# 7_VGA.net
KiCad netlist of a schematic drawn in Altium Designer
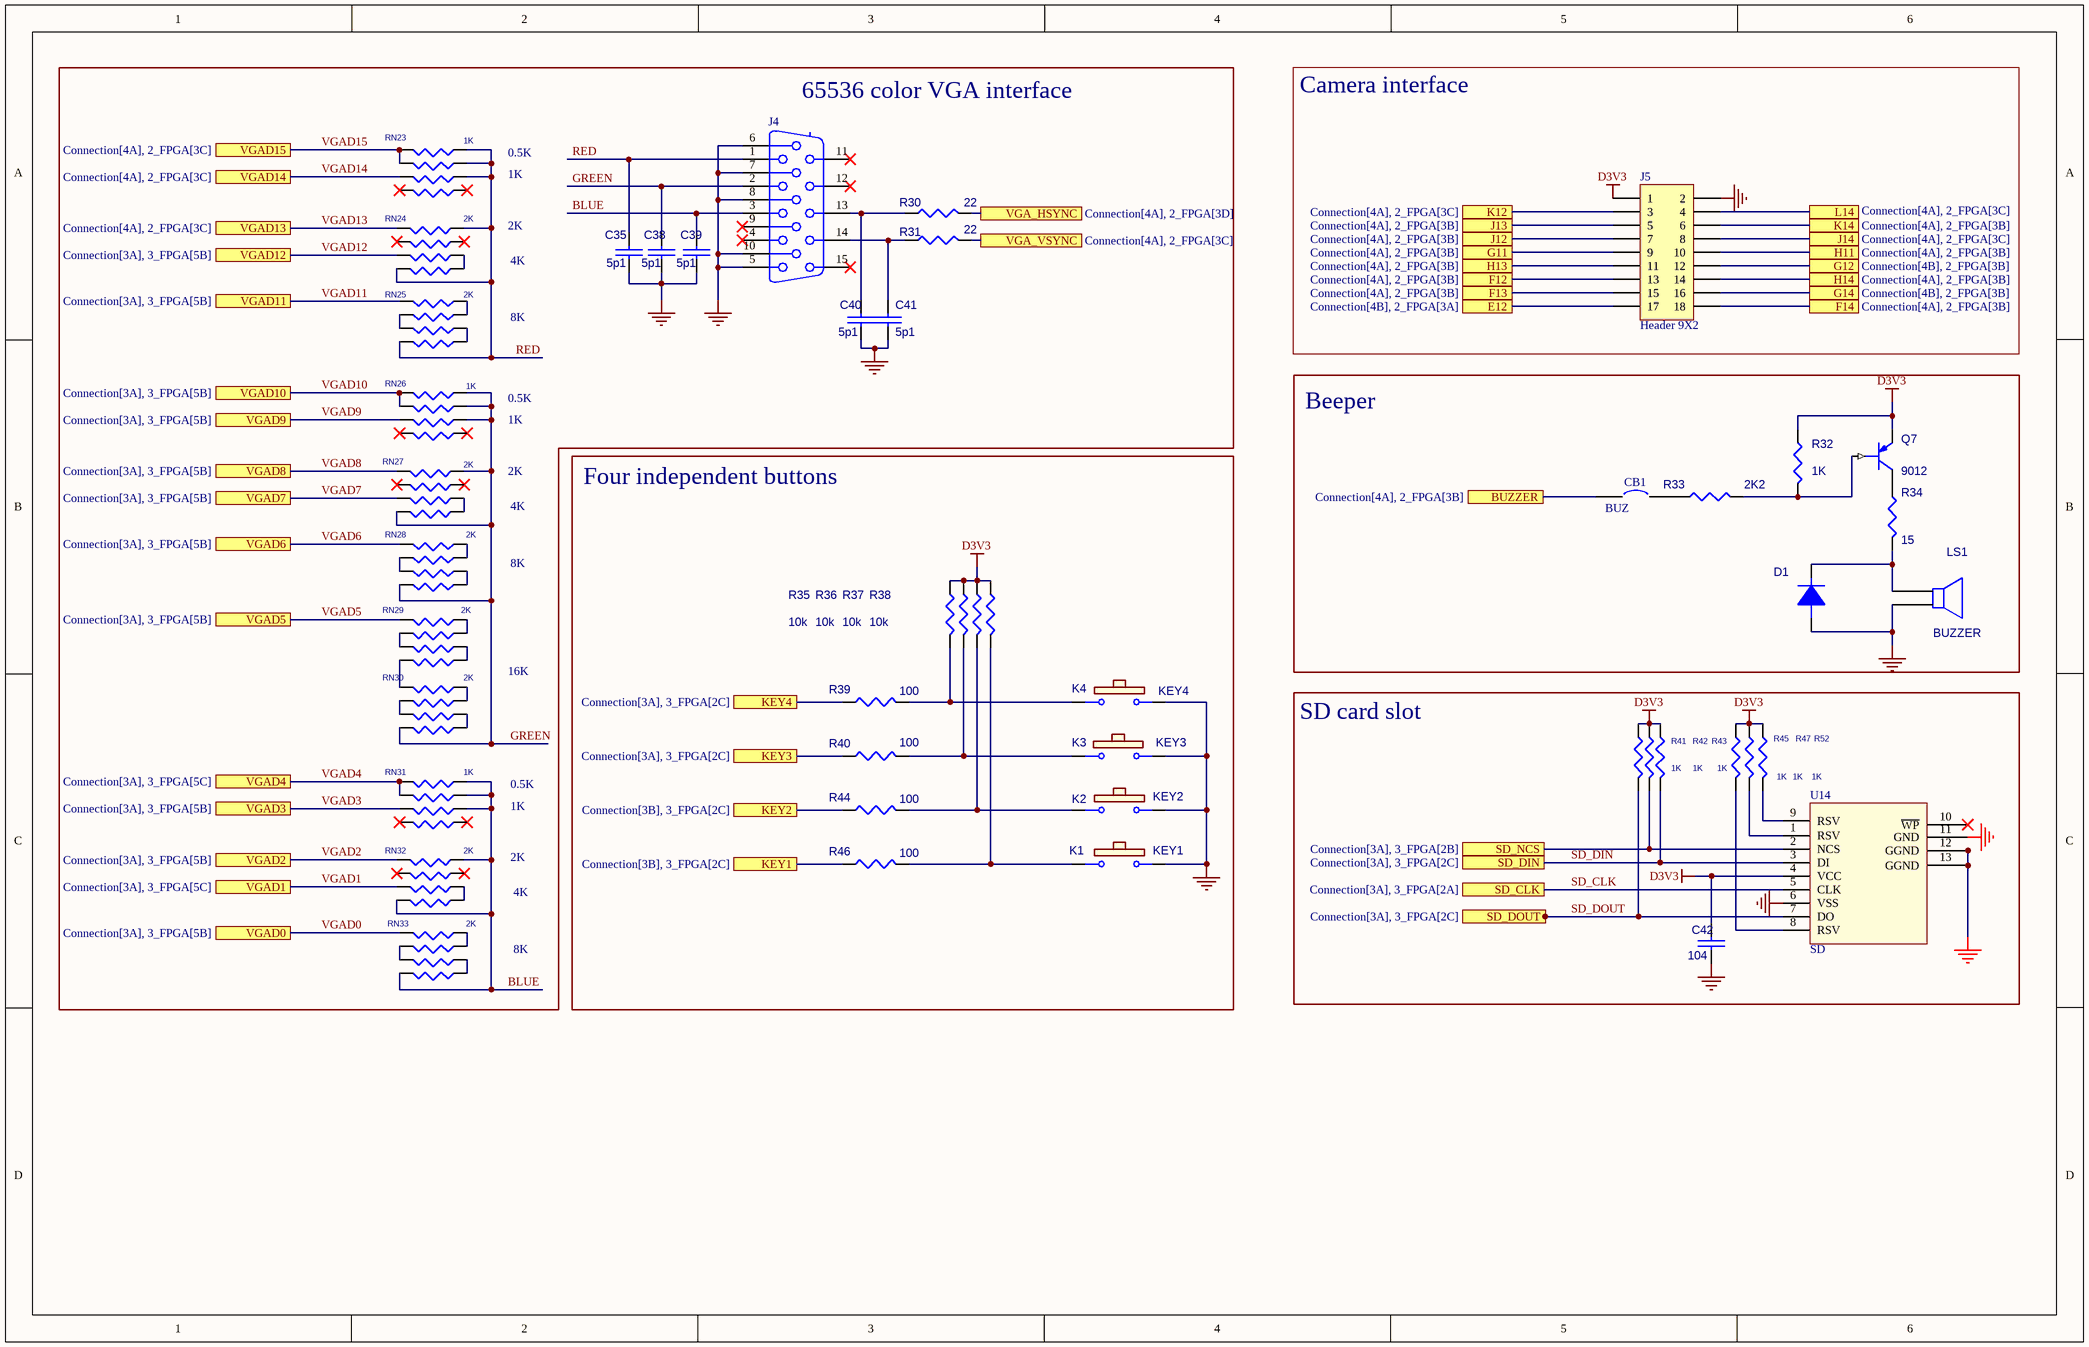
[diagram p0: 7_VGA.SchDoc]

(export (version "E")
  (design (tool "Eeschema 10.0.6"))
  (components
    (comp (ref "C35") (value "5p1") (footprint "0603 Cap") (libsource (lib "SPARTAN6") (part "C_Dup4")))
    (comp (ref "C38") (value "5p1") (footprint "0603 Cap") (libsource (lib "SPARTAN6") (part "C_Dup4")))
    (comp (ref "C39") (value "5p1") (footprint "0603 Cap") (libsource (lib "SPARTAN6") (part "C_Dup4")))
    (comp (ref "C40") (value "5p1") (footprint "0603 Cap") (libsource (lib "SPARTAN6") (part "C_Dup4")))
    (comp (ref "C41") (value "5p1") (footprint "0603 Cap") (libsource (lib "SPARTAN6") (part "C_Dup4")))
    (comp (ref "C42") (value "104") (footprint "0402 Cap") (libsource (lib "SPARTAN6") (part "C_Dup3")))
    (comp (ref "CB1")
      (value "BUZ")
      (footprint "SIP2")
      (description "Circuit Breaker")
      (fields (field (name "PUBLISHER") "Altium Limited"))
      (libsource (lib "Miscellaneous Devices") (part "Circuit Breaker"))
    )
    (comp (ref "D1") (value "~") (footprint "1206") (libsource (lib "Xilinx Spartan-6") (part "4148")))
    (comp (ref "J4")
      (value "~")
      (footprint "VGA")
      (description "Receptacle Assembly, 15-Pin, Sim Line Connector")
      (fields (field (name "PUBLISHER") "Altium Limited"))
      (libsource (lib "Xilinx Spartan-6") (part "Connector 15"))
    )
    (comp (ref "J5")
      (value "Header 9X2")
      (footprint "HDR2X9")
      (description "Header, 9-Pin, Dual row")
      (fields (field (name "PUBLISHER") "Altium Limited"))
      (libsource (lib "Miscellaneous Connectors") (part "Header 9X2"))
    )
    (comp (ref "K1") (value "KEY1") (footprint "KEY735SO") (libsource (lib "*") (part "KEYB")))
    (comp (ref "K2") (value "KEY2") (footprint "KEY735SO") (libsource (lib "*") (part "KEYB")))
    (comp (ref "K3") (value "KEY3") (footprint "KEY735SO") (libsource (lib "") (part "KEYB_1")))
    (comp (ref "K4") (value "KEY4") (footprint "KEY735SO") (libsource (lib "*") (part "KEYB")))
    (comp (ref "LS1") (value "BUZZER") (libsource (lib "*") (part "SPEAKER")))
    (comp (ref "Q7") (value "9012") (footprint "SOT23") (libsource (lib "*") (part "PNP")))
    (comp (ref "R30") (value "22") (footprint "0603") (libsource (lib "*") (part "R")))
    (comp (ref "R31") (value "22") (footprint "0603") (libsource (lib "*") (part "R")))
    (comp (ref "R32") (value "1K") (footprint "0603") (libsource (lib "*") (part "R_Dup3")))
    (comp (ref "R33") (value "2K2") (footprint "0603") (libsource (lib "*") (part "R_Dup3")))
    (comp (ref "R34") (value "15") (footprint "0603") (libsource (lib "*") (part "R_Dup3")))
    (comp (ref "R35") (value "10k") (footprint "0603") (libsource (lib "*") (part "R_Dup2")))
    (comp (ref "R36") (value "10k") (footprint "0603") (libsource (lib "*") (part "R_Dup2")))
    (comp (ref "R37") (value "10k") (footprint "0603") (libsource (lib "*") (part "R_Dup2")))
    (comp (ref "R38") (value "10k") (footprint "0603") (libsource (lib "*") (part "R_Dup2")))
    (comp (ref "R39") (value "100") (footprint "0603") (libsource (lib "*") (part "R_Dup2")))
    (comp (ref "R40") (value "100") (footprint "0603") (libsource (lib "*") (part "R_Dup2")))
    (comp (ref "R41") (value "1K") (footprint "0603") (libsource (lib "*") (part "R")))
    (comp (ref "R42") (value "1K") (footprint "0603") (libsource (lib "*") (part "R")))
    (comp (ref "R43") (value "1K") (footprint "0603") (libsource (lib "*") (part "R")))
    (comp (ref "R44") (value "100") (footprint "0603") (libsource (lib "*") (part "R_Dup2")))
    (comp (ref "R45") (value "1K") (footprint "0603") (libsource (lib "*") (part "R")))
    (comp (ref "R46") (value "100") (footprint "0603") (libsource (lib "*") (part "R_Dup2")))
    (comp (ref "R47") (value "1K") (footprint "0603") (libsource (lib "*") (part "R")))
    (comp (ref "R52") (value "1K") (footprint "0603") (libsource (lib "*") (part "R")))
    (comp (ref "RN23") (value "1K") (footprint "RN-8P") (libsource (lib "*") (part "RN_Dup1")))
    (comp (ref "RN24") (value "2K") (footprint "RN-8P") (libsource (lib "*") (part "RN_Dup1")))
    (comp (ref "RN25") (value "2K") (footprint "RN-8P") (libsource (lib "*") (part "RN_Dup1")))
    (comp (ref "RN26") (value "1K") (footprint "RN-8P") (libsource (lib "*") (part "RN_Dup1")))
    (comp (ref "RN27") (value "2K") (footprint "RN-8P") (libsource (lib "*") (part "RN_Dup1")))
    (comp (ref "RN28") (value "2K") (footprint "RN-8P") (libsource (lib "*") (part "RN_Dup1")))
    (comp (ref "RN29") (value "2K") (footprint "RN-8P") (libsource (lib "*") (part "RN_Dup1")))
    (comp (ref "RN30") (value "2K") (footprint "RN-8P") (libsource (lib "*") (part "RN_Dup1")))
    (comp (ref "RN31") (value "1K") (footprint "RN-8P") (libsource (lib "*") (part "RN_Dup1")))
    (comp (ref "RN32") (value "2K") (footprint "RN-8P") (libsource (lib "*") (part "RN_Dup1")))
    (comp (ref "RN33") (value "2K") (footprint "RN-8P") (libsource (lib "*") (part "RN_Dup1")))
    (comp (ref "U14") (value "SD") (footprint "TF") (libsource (lib "TFT") (part "SD")))
  )
  (nets
    (net (code "1") (name "/BLUE") (class "Default")
      (node (ref "C39") (pin "1") (pinfunction "1_1") (pintype "passive"))
      (node (ref "J4") (pin "3") (pinfunction "3_3") (pintype "passive"))
      (node (ref "RN31") (pin "2") (pinfunction "2_2") (pintype "passive"))
      (node (ref "RN31") (pin "3") (pinfunction "3_3") (pintype "passive"))
      (node (ref "RN31") (pin "4") (pinfunction "4_4") (pintype "passive"))
      (node (ref "RN32") (pin "4") (pinfunction "4_4") (pintype "passive"))
      (node (ref "RN32") (pin "8") (pinfunction "8_8") (pintype "passive"))
      (node (ref "RN33") (pin "8") (pinfunction "8_8") (pintype "passive"))
    )
    (net (code "2") (name "/BUZZER") (class "Default")
      (node (ref "CB1") (pin "1") (pinfunction "1_1") (pintype "passive"))
    )
    (net (code "3") (name "/E12") (class "Default")
      (node (ref "J5") (pin "17") (pinfunction "17_17") (pintype "passive"))
    )
    (net (code "4") (name "/F12") (class "Default")
      (node (ref "J5") (pin "13") (pinfunction "13_13") (pintype "passive"))
    )
    (net (code "5") (name "/F13") (class "Default")
      (node (ref "J5") (pin "15") (pinfunction "15_15") (pintype "passive"))
    )
    (net (code "6") (name "/F14") (class "Default")
      (node (ref "J5") (pin "18") (pinfunction "18_18") (pintype "passive"))
    )
    (net (code "7") (name "/G11") (class "Default")
      (node (ref "J5") (pin "9") (pinfunction "9_9") (pintype "passive"))
    )
    (net (code "8") (name "/G12") (class "Default")
      (node (ref "J5") (pin "12") (pinfunction "12_12") (pintype "passive"))
    )
    (net (code "9") (name "/G14") (class "Default")
      (node (ref "J5") (pin "16") (pinfunction "16_16") (pintype "passive"))
    )
    (net (code "10") (name "/GREEN") (class "Default")
      (node (ref "C38") (pin "1") (pinfunction "1_1") (pintype "passive"))
      (node (ref "J4") (pin "2") (pinfunction "2_2") (pintype "passive"))
      (node (ref "RN26") (pin "2") (pinfunction "2_2") (pintype "passive"))
      (node (ref "RN26") (pin "3") (pinfunction "3_3") (pintype "passive"))
      (node (ref "RN26") (pin "4") (pinfunction "4_4") (pintype "passive"))
      (node (ref "RN27") (pin "4") (pinfunction "4_4") (pintype "passive"))
      (node (ref "RN27") (pin "8") (pinfunction "8_8") (pintype "passive"))
      (node (ref "RN28") (pin "8") (pinfunction "8_8") (pintype "passive"))
      (node (ref "RN30") (pin "8") (pinfunction "8_8") (pintype "passive"))
    )
    (net (code "11") (name "/H11") (class "Default")
      (node (ref "J5") (pin "10") (pinfunction "10_10") (pintype "passive"))
    )
    (net (code "12") (name "/H13") (class "Default")
      (node (ref "J5") (pin "11") (pinfunction "11_11") (pintype "passive"))
    )
    (net (code "13") (name "/H14") (class "Default")
      (node (ref "J5") (pin "14") (pinfunction "14_14") (pintype "passive"))
    )
    (net (code "14") (name "/J12") (class "Default")
      (node (ref "J5") (pin "7") (pinfunction "7_7") (pintype "passive"))
    )
    (net (code "15") (name "/J13") (class "Default")
      (node (ref "J5") (pin "5") (pinfunction "5_5") (pintype "passive"))
    )
    (net (code "16") (name "/J14") (class "Default")
      (node (ref "J5") (pin "8") (pinfunction "8_8") (pintype "passive"))
    )
    (net (code "17") (name "/K12") (class "Default")
      (node (ref "J5") (pin "3") (pinfunction "3_3") (pintype "passive"))
    )
    (net (code "18") (name "/K14") (class "Default")
      (node (ref "J5") (pin "6") (pinfunction "6_6") (pintype "passive"))
    )
    (net (code "19") (name "/KEY1") (class "Default")
      (node (ref "R46") (pin "1") (pinfunction "1_1") (pintype "passive"))
    )
    (net (code "20") (name "/KEY2") (class "Default")
      (node (ref "R44") (pin "1") (pinfunction "1_1") (pintype "passive"))
    )
    (net (code "21") (name "/KEY3") (class "Default")
      (node (ref "R40") (pin "1") (pinfunction "1_1") (pintype "passive"))
    )
    (net (code "22") (name "/KEY4") (class "Default")
      (node (ref "R39") (pin "1") (pinfunction "1_1") (pintype "passive"))
    )
    (net (code "23") (name "/L14") (class "Default")
      (node (ref "J5") (pin "4") (pinfunction "4_4") (pintype "passive"))
    )
    (net (code "24") (name "/RED") (class "Default")
      (node (ref "C35") (pin "1") (pinfunction "1_1") (pintype "passive"))
      (node (ref "J4") (pin "1") (pinfunction "1_1") (pintype "passive"))
      (node (ref "RN23") (pin "2") (pinfunction "2_2") (pintype "passive"))
      (node (ref "RN23") (pin "3") (pinfunction "3_3") (pintype "passive"))
      (node (ref "RN23") (pin "4") (pinfunction "4_4") (pintype "passive"))
      (node (ref "RN24") (pin "4") (pinfunction "4_4") (pintype "passive"))
      (node (ref "RN24") (pin "8") (pinfunction "8_8") (pintype "passive"))
      (node (ref "RN25") (pin "8") (pinfunction "8_8") (pintype "passive"))
    )
    (net (code "25") (name "/SD_CLK") (class "Default")
      (node (ref "U14") (pin "5") (pinfunction "CLK_5") (pintype "passive"))
    )
    (net (code "26") (name "/SD_DIN") (class "Default")
      (node (ref "R43") (pin "2") (pinfunction "2_2") (pintype "passive"))
      (node (ref "U14") (pin "3") (pinfunction "DI_3") (pintype "passive"))
    )
    (net (code "27") (name "/SD_DOUT") (class "Default")
      (node (ref "R41") (pin "2") (pinfunction "2_2") (pintype "passive"))
      (node (ref "U14") (pin "7") (pinfunction "DO_7") (pintype "passive"))
    )
    (net (code "28") (name "/SD_NCS") (class "Default")
      (node (ref "R42") (pin "2") (pinfunction "2_2") (pintype "passive"))
      (node (ref "U14") (pin "2") (pinfunction "NCS_2") (pintype "passive"))
    )
    (net (code "29") (name "/VGAD0") (class "Default")
      (node (ref "RN33") (pin "5") (pinfunction "5_5") (pintype "passive"))
    )
    (net (code "30") (name "/VGAD1") (class "Default")
      (node (ref "RN32") (pin "7") (pinfunction "7_7") (pintype "passive"))
    )
    (net (code "31") (name "/VGAD2") (class "Default")
      (node (ref "RN32") (pin "5") (pinfunction "5_5") (pintype "passive"))
    )
    (net (code "32") (name "/VGAD3") (class "Default")
      (node (ref "RN31") (pin "7") (pinfunction "7_7") (pintype "passive"))
    )
    (net (code "33") (name "/VGAD4") (class "Default")
      (node (ref "RN31") (pin "5") (pinfunction "5_5") (pintype "passive"))
      (node (ref "RN31") (pin "6") (pinfunction "6_6") (pintype "passive"))
    )
    (net (code "34") (name "/VGAD5") (class "Default")
      (node (ref "RN29") (pin "5") (pinfunction "5_5") (pintype "passive"))
    )
    (net (code "35") (name "/VGAD6") (class "Default")
      (node (ref "RN28") (pin "5") (pinfunction "5_5") (pintype "passive"))
    )
    (net (code "36") (name "/VGAD7") (class "Default")
      (node (ref "RN27") (pin "7") (pinfunction "7_7") (pintype "passive"))
    )
    (net (code "37") (name "/VGAD8") (class "Default")
      (node (ref "RN27") (pin "5") (pinfunction "5_5") (pintype "passive"))
    )
    (net (code "38") (name "/VGAD9") (class "Default")
      (node (ref "RN26") (pin "7") (pinfunction "7_7") (pintype "passive"))
    )
    (net (code "39") (name "/VGAD10") (class "Default")
      (node (ref "RN26") (pin "5") (pinfunction "5_5") (pintype "passive"))
      (node (ref "RN26") (pin "6") (pinfunction "6_6") (pintype "passive"))
    )
    (net (code "40") (name "/VGAD11") (class "Default")
      (node (ref "RN25") (pin "5") (pinfunction "5_5") (pintype "passive"))
    )
    (net (code "41") (name "/VGAD12") (class "Default")
      (node (ref "RN24") (pin "7") (pinfunction "7_7") (pintype "passive"))
    )
    (net (code "42") (name "/VGAD13") (class "Default")
      (node (ref "RN24") (pin "5") (pinfunction "5_5") (pintype "passive"))
    )
    (net (code "43") (name "/VGAD14") (class "Default")
      (node (ref "RN23") (pin "7") (pinfunction "7_7") (pintype "passive"))
    )
    (net (code "44") (name "/VGAD15") (class "Default")
      (node (ref "RN23") (pin "5") (pinfunction "5_5") (pintype "passive"))
      (node (ref "RN23") (pin "6") (pinfunction "6_6") (pintype "passive"))
    )
    (net (code "45") (name "/VGA_HSYNC") (class "Default")
      (node (ref "R30") (pin "2") (pinfunction "2_2") (pintype "passive"))
    )
    (net (code "46") (name "/VGA_VSYNC") (class "Default")
      (node (ref "R31") (pin "2") (pinfunction "2_2") (pintype "passive"))
    )
    (net (code "47") (name "D3V3") (class "Default")
      (node (ref "C42") (pin "1") (pinfunction "1_1") (pintype "passive"))
      (node (ref "J5") (pin "1") (pinfunction "1_1") (pintype "passive"))
      (node (ref "Q7") (pin "2") (pinfunction "EMITTER_2") (pintype "passive"))
      (node (ref "R32") (pin "1") (pinfunction "1_1") (pintype "passive"))
      (node (ref "R35") (pin "1") (pinfunction "1_1") (pintype "passive"))
      (node (ref "R36") (pin "1") (pinfunction "1_1") (pintype "passive"))
      (node (ref "R37") (pin "1") (pinfunction "1_1") (pintype "passive"))
      (node (ref "R38") (pin "1") (pinfunction "1_1") (pintype "passive"))
      (node (ref "R41") (pin "1") (pinfunction "1_1") (pintype "passive"))
      (node (ref "R42") (pin "1") (pinfunction "1_1") (pintype "passive"))
      (node (ref "R43") (pin "1") (pinfunction "1_1") (pintype "passive"))
      (node (ref "R45") (pin "1") (pinfunction "1_1") (pintype "passive"))
      (node (ref "R47") (pin "1") (pinfunction "1_1") (pintype "passive"))
      (node (ref "R52") (pin "1") (pinfunction "1_1") (pintype "passive"))
      (node (ref "U14") (pin "4") (pinfunction "VCC_4") (pintype "passive"))
    )
    (net (code "48") (name "GND") (class "Default")
      (node (ref "C35") (pin "2") (pinfunction "2_2") (pintype "passive"))
      (node (ref "C38") (pin "2") (pinfunction "2_2") (pintype "passive"))
      (node (ref "C39") (pin "2") (pinfunction "2_2") (pintype "passive"))
      (node (ref "C40") (pin "2") (pinfunction "2_2") (pintype "passive"))
      (node (ref "C41") (pin "2") (pinfunction "2_2") (pintype "passive"))
      (node (ref "C42") (pin "2") (pinfunction "2_2") (pintype "passive"))
      (node (ref "D1") (pin "1") (pinfunction "A_1") (pintype "passive"))
      (node (ref "J4") (pin "10") (pinfunction "10_10") (pintype "passive"))
      (node (ref "J4") (pin "5") (pinfunction "5_5") (pintype "passive"))
      (node (ref "J4") (pin "6") (pinfunction "6_6") (pintype "passive"))
      (node (ref "J4") (pin "7") (pinfunction "7_7") (pintype "passive"))
      (node (ref "J4") (pin "8") (pinfunction "8_8") (pintype "passive"))
      (node (ref "J5") (pin "2") (pinfunction "2_2") (pintype "passive"))
      (node (ref "K1") (pin "2") (pinfunction "2_2") (pintype "passive"))
      (node (ref "K2") (pin "2") (pinfunction "2_2") (pintype "passive"))
      (node (ref "K3") (pin "1") (pinfunction "1_1") (pintype "passive"))
      (node (ref "K4") (pin "2") (pinfunction "2_2") (pintype "passive"))
      (node (ref "LS1") (pin "2") (pinfunction "2_2") (pintype "passive"))
      (node (ref "U14") (pin "11") (pinfunction "GND_11") (pintype "passive"))
      (node (ref "U14") (pin "12") (pinfunction "GGND_12") (pintype "passive"))
      (node (ref "U14") (pin "13") (pinfunction "GGND_13") (pintype "passive"))
      (node (ref "U14") (pin "6") (pinfunction "VSS_6") (pintype "passive"))
    )
    (net (code "49") (name "Net-(C40-Pad1)") (class "Default")
      (node (ref "C40") (pin "1") (pinfunction "1_1") (pintype "passive"))
      (node (ref "J4") (pin "13") (pinfunction "13_13") (pintype "passive"))
      (node (ref "R30") (pin "1") (pinfunction "1_1") (pintype "passive"))
    )
    (net (code "50") (name "Net-(C41-Pad1)") (class "Default")
      (node (ref "C41") (pin "1") (pinfunction "1_1") (pintype "passive"))
      (node (ref "J4") (pin "14") (pinfunction "14_14") (pintype "passive"))
      (node (ref "R31") (pin "1") (pinfunction "1_1") (pintype "passive"))
    )
    (net (code "51") (name "Net-(CB1-Pad2)") (class "Default")
      (node (ref "CB1") (pin "2") (pinfunction "2_2") (pintype "passive"))
      (node (ref "R33") (pin "1") (pinfunction "1_1") (pintype "passive"))
    )
    (net (code "52") (name "Net-(D1-C)") (class "Default")
      (node (ref "D1") (pin "2") (pinfunction "C_2") (pintype "passive"))
      (node (ref "LS1") (pin "1") (pinfunction "1_1") (pintype "passive"))
      (node (ref "R34") (pin "2") (pinfunction "2_2") (pintype "passive"))
    )
    (net (code "53") (name "Net-(K1-Pad1)") (class "Default")
      (node (ref "K1") (pin "1") (pinfunction "1_1") (pintype "passive"))
      (node (ref "R38") (pin "2") (pinfunction "2_2") (pintype "passive"))
      (node (ref "R46") (pin "2") (pinfunction "2_2") (pintype "passive"))
    )
    (net (code "54") (name "Net-(K2-Pad1)") (class "Default")
      (node (ref "K2") (pin "1") (pinfunction "1_1") (pintype "passive"))
      (node (ref "R37") (pin "2") (pinfunction "2_2") (pintype "passive"))
      (node (ref "R44") (pin "2") (pinfunction "2_2") (pintype "passive"))
    )
    (net (code "55") (name "Net-(K3-Pad2)") (class "Default")
      (node (ref "K3") (pin "2") (pinfunction "2_2") (pintype "passive"))
      (node (ref "R36") (pin "2") (pinfunction "2_2") (pintype "passive"))
      (node (ref "R40") (pin "2") (pinfunction "2_2") (pintype "passive"))
    )
    (net (code "56") (name "Net-(K4-Pad1)") (class "Default")
      (node (ref "K4") (pin "1") (pinfunction "1_1") (pintype "passive"))
      (node (ref "R35") (pin "2") (pinfunction "2_2") (pintype "passive"))
      (node (ref "R39") (pin "2") (pinfunction "2_2") (pintype "passive"))
    )
    (net (code "57") (name "Net-(Q7-BASE)") (class "Default")
      (node (ref "Q7") (pin "1") (pinfunction "BASE_1") (pintype "input"))
      (node (ref "R32") (pin "2") (pinfunction "2_2") (pintype "passive"))
      (node (ref "R33") (pin "2") (pinfunction "2_2") (pintype "passive"))
    )
    (net (code "58") (name "Net-(Q7-COLLECTOR)") (class "Default")
      (node (ref "Q7") (pin "3") (pinfunction "COLLECTOR_3") (pintype "passive"))
      (node (ref "R34") (pin "1") (pinfunction "1_1") (pintype "passive"))
    )
    (net (code "59") (name "Net-(R45-Pad2)") (class "Default")
      (node (ref "R45") (pin "2") (pinfunction "2_2") (pintype "passive"))
      (node (ref "U14") (pin "8") (pinfunction "RSV_8") (pintype "passive"))
    )
    (net (code "60") (name "Net-(R47-Pad2)") (class "Default")
      (node (ref "R47") (pin "2") (pinfunction "2_2") (pintype "passive"))
      (node (ref "U14") (pin "1") (pinfunction "RSV_1") (pintype "passive"))
    )
    (net (code "61") (name "Net-(R52-Pad2)") (class "Default")
      (node (ref "R52") (pin "2") (pinfunction "2_2") (pintype "passive"))
      (node (ref "U14") (pin "9") (pinfunction "RSV_9") (pintype "passive"))
    )
    (net (code "62") (name "Net-(RN24-Pad1)") (class "Default")
      (node (ref "RN24") (pin "1") (pinfunction "1_1") (pintype "passive"))
      (node (ref "RN24") (pin "2") (pinfunction "2_2") (pintype "passive"))
    )
    (net (code "63") (name "Net-(RN25-Pad1)") (class "Default")
      (node (ref "RN25") (pin "1") (pinfunction "1_1") (pintype "passive"))
      (node (ref "RN25") (pin "2") (pinfunction "2_2") (pintype "passive"))
    )
    (net (code "64") (name "Net-(RN25-Pad3)") (class "Default")
      (node (ref "RN25") (pin "3") (pinfunction "3_3") (pintype "passive"))
      (node (ref "RN25") (pin "4") (pinfunction "4_4") (pintype "passive"))
    )
    (net (code "65") (name "Net-(RN25-Pad6)") (class "Default")
      (node (ref "RN25") (pin "6") (pinfunction "6_6") (pintype "passive"))
      (node (ref "RN25") (pin "7") (pinfunction "7_7") (pintype "passive"))
    )
    (net (code "66") (name "Net-(RN27-Pad1)") (class "Default")
      (node (ref "RN27") (pin "1") (pinfunction "1_1") (pintype "passive"))
      (node (ref "RN27") (pin "2") (pinfunction "2_2") (pintype "passive"))
    )
    (net (code "67") (name "Net-(RN28-Pad1)") (class "Default")
      (node (ref "RN28") (pin "1") (pinfunction "1_1") (pintype "passive"))
      (node (ref "RN28") (pin "2") (pinfunction "2_2") (pintype "passive"))
    )
    (net (code "68") (name "Net-(RN28-Pad3)") (class "Default")
      (node (ref "RN28") (pin "3") (pinfunction "3_3") (pintype "passive"))
      (node (ref "RN28") (pin "4") (pinfunction "4_4") (pintype "passive"))
    )
    (net (code "69") (name "Net-(RN28-Pad6)") (class "Default")
      (node (ref "RN28") (pin "6") (pinfunction "6_6") (pintype "passive"))
      (node (ref "RN28") (pin "7") (pinfunction "7_7") (pintype "passive"))
    )
    (net (code "70") (name "Net-(RN29-Pad1)") (class "Default")
      (node (ref "RN29") (pin "1") (pinfunction "1_1") (pintype "passive"))
      (node (ref "RN29") (pin "2") (pinfunction "2_2") (pintype "passive"))
    )
    (net (code "71") (name "Net-(RN29-Pad3)") (class "Default")
      (node (ref "RN29") (pin "3") (pinfunction "3_3") (pintype "passive"))
      (node (ref "RN29") (pin "4") (pinfunction "4_4") (pintype "passive"))
    )
    (net (code "72") (name "Net-(RN29-Pad6)") (class "Default")
      (node (ref "RN29") (pin "6") (pinfunction "6_6") (pintype "passive"))
      (node (ref "RN29") (pin "7") (pinfunction "7_7") (pintype "passive"))
    )
    (net (code "73") (name "Net-(RN29-Pad8)") (class "Default")
      (node (ref "RN29") (pin "8") (pinfunction "8_8") (pintype "passive"))
      (node (ref "RN30") (pin "5") (pinfunction "5_5") (pintype "passive"))
    )
    (net (code "74") (name "Net-(RN30-Pad1)") (class "Default")
      (node (ref "RN30") (pin "1") (pinfunction "1_1") (pintype "passive"))
      (node (ref "RN30") (pin "2") (pinfunction "2_2") (pintype "passive"))
    )
    (net (code "75") (name "Net-(RN30-Pad3)") (class "Default")
      (node (ref "RN30") (pin "3") (pinfunction "3_3") (pintype "passive"))
      (node (ref "RN30") (pin "4") (pinfunction "4_4") (pintype "passive"))
    )
    (net (code "76") (name "Net-(RN30-Pad6)") (class "Default")
      (node (ref "RN30") (pin "6") (pinfunction "6_6") (pintype "passive"))
      (node (ref "RN30") (pin "7") (pinfunction "7_7") (pintype "passive"))
    )
    (net (code "77") (name "Net-(RN32-Pad1)") (class "Default")
      (node (ref "RN32") (pin "1") (pinfunction "1_1") (pintype "passive"))
      (node (ref "RN32") (pin "2") (pinfunction "2_2") (pintype "passive"))
    )
    (net (code "78") (name "Net-(RN33-Pad1)") (class "Default")
      (node (ref "RN33") (pin "1") (pinfunction "1_1") (pintype "passive"))
      (node (ref "RN33") (pin "2") (pinfunction "2_2") (pintype "passive"))
    )
    (net (code "79") (name "Net-(RN33-Pad3)") (class "Default")
      (node (ref "RN33") (pin "3") (pinfunction "3_3") (pintype "passive"))
      (node (ref "RN33") (pin "4") (pinfunction "4_4") (pintype "passive"))
    )
    (net (code "80") (name "Net-(RN33-Pad6)") (class "Default")
      (node (ref "RN33") (pin "6") (pinfunction "6_6") (pintype "passive"))
      (node (ref "RN33") (pin "7") (pinfunction "7_7") (pintype "passive"))
    )
    (net (code "81") (name "unconnected-(J4-MH1-Pad16)") (class "Default")
      (node (ref "J4") (pin "16") (pinfunction "MH1_16") (pintype "passive"))
    )
    (net (code "82") (name "unconnected-(J4-MH2-Pad17)") (class "Default")
      (node (ref "J4") (pin "17") (pinfunction "MH2_17") (pintype "passive"))
    )
    (net (code "83") (name "unconnected-(J4-Pad4)") (class "Default")
      (node (ref "J4") (pin "4") (pinfunction "4_4") (pintype "passive+no_connect"))
    )
    (net (code "84") (name "unconnected-(J4-Pad9)") (class "Default")
      (node (ref "J4") (pin "9") (pinfunction "9_9") (pintype "passive+no_connect"))
    )
    (net (code "85") (name "unconnected-(J4-Pad11)") (class "Default")
      (node (ref "J4") (pin "11") (pinfunction "11_11") (pintype "passive+no_connect"))
    )
    (net (code "86") (name "unconnected-(J4-Pad12)") (class "Default")
      (node (ref "J4") (pin "12") (pinfunction "12_12") (pintype "passive+no_connect"))
    )
    (net (code "87") (name "unconnected-(J4-Pad15)") (class "Default")
      (node (ref "J4") (pin "15") (pinfunction "15_15") (pintype "passive+no_connect"))
    )
    (net (code "88") (name "unconnected-(RN23-Pad1)") (class "Default")
      (node (ref "RN23") (pin "1") (pinfunction "1_1") (pintype "passive+no_connect"))
    )
    (net (code "89") (name "unconnected-(RN23-Pad8)") (class "Default")
      (node (ref "RN23") (pin "8") (pinfunction "8_8") (pintype "passive+no_connect"))
    )
    (net (code "90") (name "unconnected-(RN24-Pad3)") (class "Default")
      (node (ref "RN24") (pin "3") (pinfunction "3_3") (pintype "passive+no_connect"))
    )
    (net (code "91") (name "unconnected-(RN24-Pad6)") (class "Default")
      (node (ref "RN24") (pin "6") (pinfunction "6_6") (pintype "passive+no_connect"))
    )
    (net (code "92") (name "unconnected-(RN26-Pad1)") (class "Default")
      (node (ref "RN26") (pin "1") (pinfunction "1_1") (pintype "passive+no_connect"))
    )
    (net (code "93") (name "unconnected-(RN26-Pad8)") (class "Default")
      (node (ref "RN26") (pin "8") (pinfunction "8_8") (pintype "passive+no_connect"))
    )
    (net (code "94") (name "unconnected-(RN27-Pad3)") (class "Default")
      (node (ref "RN27") (pin "3") (pinfunction "3_3") (pintype "passive+no_connect"))
    )
    (net (code "95") (name "unconnected-(RN27-Pad6)") (class "Default")
      (node (ref "RN27") (pin "6") (pinfunction "6_6") (pintype "passive+no_connect"))
    )
    (net (code "96") (name "unconnected-(RN31-Pad1)") (class "Default")
      (node (ref "RN31") (pin "1") (pinfunction "1_1") (pintype "passive+no_connect"))
    )
    (net (code "97") (name "unconnected-(RN31-Pad8)") (class "Default")
      (node (ref "RN31") (pin "8") (pinfunction "8_8") (pintype "passive+no_connect"))
    )
    (net (code "98") (name "unconnected-(RN32-Pad3)") (class "Default")
      (node (ref "RN32") (pin "3") (pinfunction "3_3") (pintype "passive+no_connect"))
    )
    (net (code "99") (name "unconnected-(RN32-Pad6)") (class "Default")
      (node (ref "RN32") (pin "6") (pinfunction "6_6") (pintype "passive+no_connect"))
    )
    (net (code "100") (name "unconnected-(U14-~{WP}-Pad10)") (class "Default")
      (node (ref "U14") (pin "10") (pinfunction "~{WP}_10") (pintype "passive+no_connect"))
    )
  )
)
